# receiver.net
KiCad netlist of a schematic drawn in EAGLE
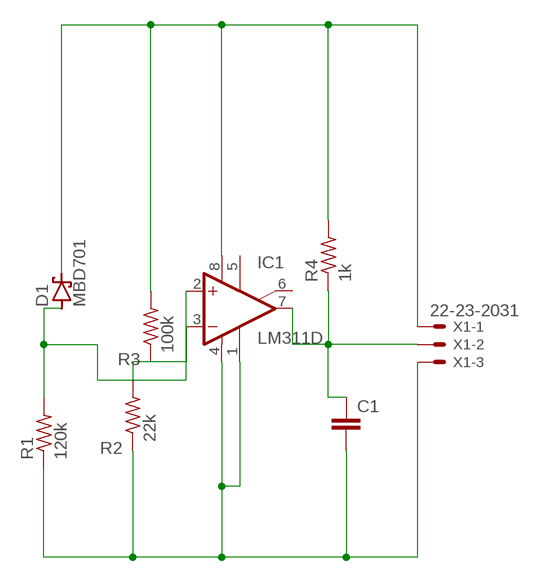
[diagram p0: schematic, sheet 1]

(export (version "E")
  (design (tool "Eeschema 10.0.6"))
  (components
    (comp (ref "C1")
      (value "C2.5/2")
      (footprint "eagle-import:C2.5-2")
      (libsource (lib "eagle-import") (part "C2.5/2"))
    )
    (comp (ref "D1")
      (value "MBD701")
      (footprint "eagle-import:TO92H")
      (libsource (lib "eagle-import") (part "MBD701"))
    )
    (comp (ref "IC1")
      (value "LM311D")
      (footprint "eagle-import:SO08")
      (libsource (lib "eagle-import") (part "LM311D"))
    )
    (comp (ref "R1")
      (value "120k")
      (footprint "eagle-import:0207_10")
      (libsource (lib "eagle-import") (part "R-US_0207/10"))
    )
    (comp (ref "R2")
      (value "22k")
      (footprint "eagle-import:0207_10")
      (libsource (lib "eagle-import") (part "R-US_0207/10"))
    )
    (comp (ref "R3")
      (value "100k")
      (footprint "eagle-import:0207_10")
      (libsource (lib "eagle-import") (part "R-US_0207/10"))
    )
    (comp (ref "R4")
      (value "1k")
      (footprint "eagle-import:0207_10")
      (libsource (lib "eagle-import") (part "R-US_0207/10"))
    )
    (comp (ref "X1")
      (value "22-23-2031")
      (footprint "eagle-import:22-23-2031")
      (fields (field (name "MF") "MOLEX"))
      (libsource (lib "eagle-import") (part "22-23-2031"))
    )
  )
  (nets
    (net (code "1") (name "Net-(D1-A)") (class "Default")
      (node (ref "D1") (pin "1") (pinfunction "A_1") (pintype "passive"))
      (node (ref "IC1") (pin "2") (pinfunction "+IN_2") (pintype "input"))
      (node (ref "R1") (pin "2") (pinfunction "2_2") (pintype "passive"))
    )
    (net (code "2") (name "Net-(D1-C)") (class "Default")
      (node (ref "D1") (pin "2") (pinfunction "C_2") (pintype "passive"))
      (node (ref "IC1") (pin "8") (pinfunction "V+_8") (pintype "power_in"))
      (node (ref "R3") (pin "2") (pinfunction "2_2") (pintype "passive"))
      (node (ref "R4") (pin "2") (pinfunction "2_2") (pintype "passive"))
      (node (ref "X1") (pin "1") (pinfunction "S_1") (pintype "passive"))
    )
    (net (code "3") (name "Net-(IC1--IN)") (class "Default")
      (node (ref "IC1") (pin "3") (pinfunction "-IN_3") (pintype "input"))
      (node (ref "R2") (pin "2") (pinfunction "2_2") (pintype "passive"))
      (node (ref "R3") (pin "1") (pinfunction "1_1") (pintype "passive"))
    )
    (net (code "4") (name "Net-(IC1-GND)") (class "Default")
      (node (ref "C1") (pin "2") (pinfunction "2_2") (pintype "passive"))
      (node (ref "IC1") (pin "1") (pinfunction "GND_1") (pintype "passive"))
      (node (ref "IC1") (pin "4") (pinfunction "V-_4") (pintype "power_in"))
      (node (ref "R1") (pin "1") (pinfunction "1_1") (pintype "passive"))
      (node (ref "R2") (pin "1") (pinfunction "1_1") (pintype "passive"))
      (node (ref "X1") (pin "3") (pinfunction "S_3") (pintype "passive"))
    )
    (net (code "5") (name "Net-(IC1-OUT)") (class "Default")
      (node (ref "C1") (pin "1") (pinfunction "1_1") (pintype "passive"))
      (node (ref "IC1") (pin "7") (pinfunction "OUT_7") (pintype "output"))
      (node (ref "R4") (pin "1") (pinfunction "1_1") (pintype "passive"))
      (node (ref "X1") (pin "2") (pinfunction "S_2") (pintype "passive"))
    )
    (net (code "6") (name "unconnected-(IC1-ON-Pad5)") (class "Default")
      (node (ref "IC1") (pin "5") (pinfunction "ON_5") (pintype "passive"))
    )
    (net (code "7") (name "unconnected-(IC1-ON{slash}STR-Pad6)") (class "Default")
      (node (ref "IC1") (pin "6") (pinfunction "ON/STR_6") (pintype "passive"))
    )
  )
)
